# Sheet.net
KiCad netlist of a schematic drawn in Altium Designer
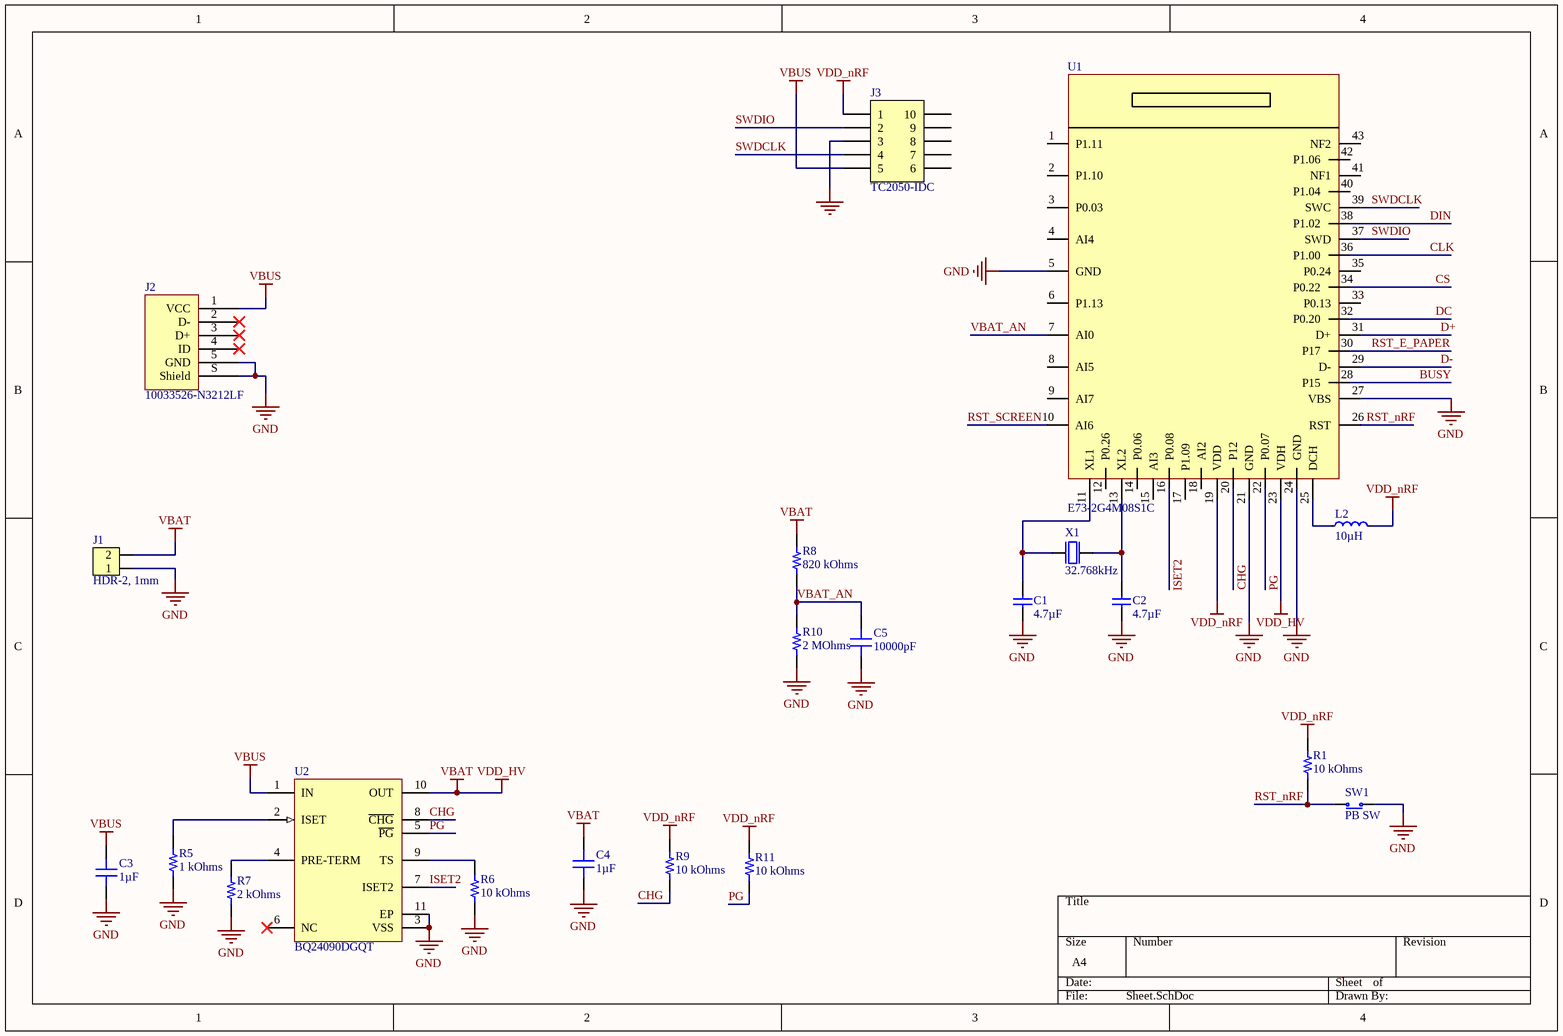
[diagram p0: Sheet.SchDoc]

(export (version "E")
  (design (tool "Eeschema 10.0.6"))
  (components
    (comp (ref "C1")
      (value "4.7µF")
      (footprint "CAPC1608X06L")
      (description "Capacitor, X7R, ±10%")
      (fields
        (field (name "PART NUMBER") "C0603-4µ7-6.3V-X7R")
        (field (name "MANUFACTURER") "Samsung")
        (field (name "PUBLISHER") "Nordic Semiconductor")
      )
      (libsource (lib "pca10056") (part "CAP_0603"))
    )
    (comp (ref "C2")
      (value "4.7µF")
      (footprint "CAPC1608X06L")
      (description "Capacitor, X7R, ±10%")
      (fields
        (field (name "PART NUMBER") "C0603-4µ7-6.3V-X7R")
        (field (name "MANUFACTURER") "Samsung")
        (field (name "PUBLISHER") "Nordic Semiconductor")
      )
      (libsource (lib "pca10056") (part "CAP_0603"))
    )
    (comp (ref "C3")
      (value "1µF")
      (footprint "CAP 0603_1608")
      (description "CAP CER 1UF 6.3V X5R 0603")
      (fields (field (name "PART NUMBER") "JMK107BJ105KK-T") (field (name "MANUFACTURER") "Taiyo Yuden"))
      (libsource (lib "Celestial Altium Library - altium_library") (part "Capacitor"))
    )
    (comp (ref "C4")
      (value "1µF")
      (footprint "CAP 0603_1608")
      (description "CAP CER 1UF 6.3V X5R 0603")
      (fields (field (name "PART NUMBER") "JMK107BJ105KK-T") (field (name "MANUFACTURER") "Taiyo Yuden"))
      (libsource (lib "Celestial Altium Library - altium_library") (part "Capacitor"))
    )
    (comp (ref "C5")
      (value "10000pF")
      (footprint "CAP 0603_1608")
      (description "CAP CER 0603 10NF 16V X7R 10%")
      (fields (field (name "PART NUMBER") "C0603C103K4RECAUTO") (field (name "MANUFACTURER") "KEMET"))
      (libsource (lib "Celestial Altium Library - altium_library") (part "Capacitor"))
    )
    (comp (ref "J1")
      (value "HDR-2, 1mm")
      (footprint "SM02B-SRSS-TB")
      (description "1.0mm pitch connector side entry SMD")
      (fields
        (field (name "PART NUMBER") "SM02B-SRSS-TB")
        (field (name "MANUFACTURER") "JST")
        (field (name "PUBLISHER") "Nordic Semiconductor")
      )
      (libsource (lib "pca10056") (part "SM02B-SRSS-TB"))
    )
    (comp (ref "J2")
      (value "10033526-N3212LF")
      (footprint "FCI USB 10033526-N3212LF")
      (description "CONN RCPT MINI USB B 5POS SMD RA")
      (fields (field (name "MANUFACTURER") "Amphenol ICC (FCI)"))
      (libsource (lib "Celestial Altium Library - altium_library") (part "USB 2.0 Type B Micro"))
    )
    (comp (ref "J3")
      (value "TC2050-IDC")
      (footprint "TC2050-IDC-NLFP")
      (description "CBL PLUG-OF-NAILS 10-PIN")
      (fields
        (field (name "PART NUMBER") "TC2050-IDC-NLFP")
        (field (name "MANUFACTURER") "Tag-Connect LLC")
        (field (name "PUBLISHER") "Nordic Semiconductor")
      )
      (libsource (lib "pca10059") (part "TC2050-IDC"))
    )
    (comp (ref "L2")
      (value "10µH")
      (footprint "INDC1608X06L")
      (description "Inductor, 80mA, ±10%")
      (fields
        (field (name "PART NUMBER") "L0603-10µ")
        (field (name "MANUFACTURER") "Taiyo Yuden")
        (field (name "PUBLISHER") "Nordic Semiconductor")
      )
      (libsource (lib "pca10059") (part "IND_0603"))
    )
    (comp (ref "R1")
      (value "10 kOhms")
      (footprint "RES 0603_1608")
      (description "RES 10K OHM 0.1% 1/16W 0603")
      (fields
        (field (name "PART NUMBER") "RNCS0603BKE10K0")
        (field (name "MANUFACTURER") "Stackpole Electronics Inc")
      )
      (libsource (lib "Celestial Altium Library - altium_library") (part "Resistor"))
    )
    (comp (ref "R5")
      (value "1 kOhms")
      (footprint "RES 0603_1608")
      (description "RES SMD 1K OHM 0.1% 1/16W 0603")
      (fields
        (field (name "PART NUMBER") "CPF0603B1K0E")
        (field (name "MANUFACTURER") "TE Connectivity Passive Product")
      )
      (libsource (lib "Celestial Altium Library - altium_library") (part "Resistor"))
    )
    (comp (ref "R6")
      (value "10 kOhms")
      (footprint "RES 0603_1608")
      (description "RES 10K OHM 0.1% 1/16W 0603")
      (fields
        (field (name "PART NUMBER") "RNCS0603BKE10K0")
        (field (name "MANUFACTURER") "Stackpole Electronics Inc")
      )
      (libsource (lib "Celestial Altium Library - altium_library") (part "Resistor"))
    )
    (comp (ref "R7")
      (value "2 kOhms")
      (footprint "RES 0603_1608")
      (description "RES SMD 2K OHM 0.1% 1/10W 0603")
      (fields (field (name "PART NUMBER") "RT0603BRD072KL") (field (name "MANUFACTURER") "Yageo"))
      (libsource (lib "Celestial Altium Library - altium_library") (part "Resistor"))
    )
    (comp (ref "R8")
      (value "820 kOhms")
      (footprint "RES 0603_1608")
      (description "CRGP 0603 820K 1%")
      (fields
        (field (name "PART NUMBER") "CRGP0603F820K")
        (field (name "MANUFACTURER") "TE Connectivity Passive Product")
      )
      (libsource (lib "Celestial Altium Library - altium_library") (part "Resistor"))
    )
    (comp (ref "R9")
      (value "10 kOhms")
      (footprint "RES 0603_1608")
      (description "RES 10K OHM 0.1% 1/16W 0603")
      (fields
        (field (name "PART NUMBER") "RNCS0603BKE10K0")
        (field (name "MANUFACTURER") "Stackpole Electronics Inc")
      )
      (libsource (lib "Celestial Altium Library - altium_library") (part "Resistor"))
    )
    (comp (ref "R10")
      (value "2 MOhms")
      (footprint "RES 0603_1608")
      (description "RES 2M OHM 1% 1/10W 0603")
      (fields
        (field (name "PART NUMBER") "RMCF0603FT2M00")
        (field (name "MANUFACTURER") "Stackpole Electronics Inc")
      )
      (libsource (lib "Celestial Altium Library - altium_library") (part "Resistor"))
    )
    (comp (ref "R11")
      (value "10 kOhms")
      (footprint "RES 0603_1608")
      (description "RES 10K OHM 0.1% 1/16W 0603")
      (fields
        (field (name "PART NUMBER") "RNCS0603BKE10K0")
        (field (name "MANUFACTURER") "Stackpole Electronics Inc")
      )
      (libsource (lib "Celestial Altium Library - altium_library") (part "Resistor"))
    )
    (comp (ref "SW1")
      (value "PB SW")
      (footprint "Switch-PB-6.2x6.3mm-SMD")
      (description "Tactile Switch, SPNO, SMD, 160gf, 6.2x6.3x2.5mm")
      (fields
        (field (name "PART NUMBER") "Switch-PB-6.2x6.3mm-SMD")
        (field (name "MANUFACTURER") "Dailywell")
        (field (name "PUBLISHER") "Nordic Semiconductor")
      )
      (libsource (lib "pca10056") (part "Switch-PB-6.2x6.3mm-SMD"))
    )
    (comp (ref "U1")
      (value "E73-2G4M08S1C")
      (footprint "E73-2G4M08S1C")
      (libsource (lib "E73-2G4M08S1C") (part "E73-2G4M08S1C"))
    )
    (comp (ref "U2")
      (value "BQ24090DGQT")
      (footprint "DGQ0010D_M")
      (fields (field (name "MANUFACTURER") "Texas Instruments"))
      (libsource (lib "Altium Content Vault") (part "TI-BQ24090DGQ10-1675X1445TP"))
    )
    (comp (ref "X1")
      (value "32.768kHz")
      (footprint "XTAL_3215")
      (description "XTAL SMD 2012, 32.768kHz, 9pF, ±20ppm")
      (fields
        (field (name "PART NUMBER") "XTAL_SMD3215_32.768kHz_9pF_NDK")
        (field (name "MANUFACTURER") "NDK")
        (field (name "PUBLISHER") "Nordic Semiconductor")
      )
      (libsource (lib "pca10056") (part "XTAL_SMD3215"))
    )
  )
  (nets
    (net (code "1") (name "/BUSY") (class "Default")
      (node (ref "U1") (pin "28") (pinfunction "P15_28") (pintype "passive"))
    )
    (net (code "2") (name "/CHG") (class "Default")
      (node (ref "R9") (pin "2") (pinfunction "2_2") (pintype "passive"))
      (node (ref "U1") (pin "20") (pinfunction "P12_20") (pintype "passive"))
      (node (ref "U2") (pin "8") (pinfunction "~{CHG}_8") (pintype "tri_state"))
    )
    (net (code "3") (name "/CLK") (class "Default")
      (node (ref "U1") (pin "36") (pinfunction "P1.00_36") (pintype "passive"))
    )
    (net (code "4") (name "/CS") (class "Default")
      (node (ref "U1") (pin "34") (pinfunction "P0.22_34") (pintype "passive"))
    )
    (net (code "5") (name "/D+") (class "Default")
      (node (ref "U1") (pin "31") (pinfunction "D+_31") (pintype "passive"))
    )
    (net (code "6") (name "/D-") (class "Default")
      (node (ref "U1") (pin "29") (pinfunction "D-_29") (pintype "passive"))
    )
    (net (code "7") (name "/DC") (class "Default")
      (node (ref "U1") (pin "32") (pinfunction "P0.20_32") (pintype "passive"))
    )
    (net (code "8") (name "/DIN") (class "Default")
      (node (ref "U1") (pin "38") (pinfunction "P1.02_38") (pintype "passive"))
    )
    (net (code "9") (name "/ISET2") (class "Default")
      (node (ref "U1") (pin "16") (pinfunction "P0.08_16") (pintype "passive"))
      (node (ref "U2") (pin "7") (pinfunction "ISET2_7") (pintype "passive"))
    )
    (net (code "10") (name "/PG") (class "Default")
      (node (ref "R11") (pin "2") (pinfunction "2_2") (pintype "passive"))
      (node (ref "U1") (pin "22") (pinfunction "P0.07_22") (pintype "passive"))
      (node (ref "U2") (pin "5") (pinfunction "~{PG}_5") (pintype "tri_state"))
    )
    (net (code "11") (name "/RST_E_PAPER") (class "Default")
      (node (ref "U1") (pin "30") (pinfunction "P17_30") (pintype "passive"))
    )
    (net (code "12") (name "/RST_SCREEN") (class "Default")
      (node (ref "U1") (pin "10") (pinfunction "AI6_10") (pintype "passive"))
    )
    (net (code "13") (name "/RST_nRF") (class "Default")
      (node (ref "R1") (pin "2") (pinfunction "2_2") (pintype "passive"))
      (node (ref "SW1") (pin "1") (pinfunction "N.O_1") (pintype "passive"))
      (node (ref "U1") (pin "26") (pinfunction "RST_26") (pintype "passive"))
    )
    (net (code "14") (name "/SWDCLK") (class "Default")
      (node (ref "J3") (pin "4") (pinfunction "4_4") (pintype "passive"))
      (node (ref "U1") (pin "39") (pinfunction "SWC_39") (pintype "passive"))
    )
    (net (code "15") (name "/SWDIO") (class "Default")
      (node (ref "J3") (pin "2") (pinfunction "2_2") (pintype "passive"))
      (node (ref "U1") (pin "37") (pinfunction "SWD_37") (pintype "passive"))
    )
    (net (code "16") (name "/VBAT_AN") (class "Default")
      (node (ref "C5") (pin "2") (pinfunction "2_2") (pintype "passive"))
      (node (ref "R10") (pin "2") (pinfunction "2_2") (pintype "passive"))
      (node (ref "R8") (pin "1") (pinfunction "1_1") (pintype "passive"))
      (node (ref "U1") (pin "7") (pinfunction "AI0_7") (pintype "passive"))
    )
    (net (code "17") (name "GND") (class "Default")
      (node (ref "C1") (pin "1") (pinfunction "1_1") (pintype "passive"))
      (node (ref "C2") (pin "1") (pinfunction "1_1") (pintype "passive"))
      (node (ref "C3") (pin "1") (pinfunction "1_1") (pintype "passive"))
      (node (ref "C4") (pin "1") (pinfunction "1_1") (pintype "passive"))
      (node (ref "C5") (pin "1") (pinfunction "1_1") (pintype "passive"))
      (node (ref "J1") (pin "1") (pinfunction "1_1") (pintype "passive"))
      (node (ref "J2") (pin "5") (pinfunction "GND_5") (pintype "passive"))
      (node (ref "J2") (pin "S") (pinfunction "Shield_S") (pintype "passive"))
      (node (ref "J3") (pin "3") (pinfunction "3_3") (pintype "passive"))
      (node (ref "R10") (pin "1") (pinfunction "1_1") (pintype "passive"))
      (node (ref "R5") (pin "1") (pinfunction "1_1") (pintype "passive"))
      (node (ref "R6") (pin "1") (pinfunction "1_1") (pintype "passive"))
      (node (ref "R7") (pin "1") (pinfunction "1_1") (pintype "passive"))
      (node (ref "SW1") (pin "2") (pinfunction "COM_2") (pintype "passive"))
      (node (ref "U1") (pin "21") (pinfunction "GND_21") (pintype "passive"))
      (node (ref "U1") (pin "24") (pinfunction "GND_24") (pintype "passive"))
      (node (ref "U1") (pin "27") (pinfunction "VBS_27") (pintype "passive"))
      (node (ref "U1") (pin "5") (pinfunction "GND_5") (pintype "passive"))
      (node (ref "U2") (pin "11") (pinfunction "EP_11") (pintype "power_in"))
      (node (ref "U2") (pin "3") (pinfunction "VSS_3") (pintype "power_in"))
    )
    (net (code "18") (name "Net-(U1-DCH)") (class "Default")
      (node (ref "L2") (pin "1") (pinfunction "1_1") (pintype "passive"))
      (node (ref "U1") (pin "25") (pinfunction "DCH_25") (pintype "passive"))
    )
    (net (code "19") (name "Net-(U1-XL1)") (class "Default")
      (node (ref "C1") (pin "2") (pinfunction "2_2") (pintype "passive"))
      (node (ref "U1") (pin "11") (pinfunction "XL1_11") (pintype "passive"))
      (node (ref "X1") (pin "1") (pinfunction "inp_1") (pintype "passive"))
    )
    (net (code "20") (name "Net-(U1-XL2)") (class "Default")
      (node (ref "C2") (pin "2") (pinfunction "2_2") (pintype "passive"))
      (node (ref "U1") (pin "13") (pinfunction "XL2_13") (pintype "passive"))
      (node (ref "X1") (pin "2") (pinfunction "out_2") (pintype "passive"))
    )
    (net (code "21") (name "Net-(U2-ISET)") (class "Default")
      (node (ref "R5") (pin "2") (pinfunction "2_2") (pintype "passive"))
      (node (ref "U2") (pin "2") (pinfunction "ISET_2") (pintype "input"))
    )
    (net (code "22") (name "Net-(U2-PRE-TERM)") (class "Default")
      (node (ref "R7") (pin "2") (pinfunction "2_2") (pintype "passive"))
      (node (ref "U2") (pin "4") (pinfunction "PRE-TERM_4") (pintype "passive"))
    )
    (net (code "23") (name "Net-(U2-TS)") (class "Default")
      (node (ref "R6") (pin "2") (pinfunction "2_2") (pintype "passive"))
      (node (ref "U2") (pin "9") (pinfunction "TS_9") (pintype "passive"))
    )
    (net (code "24") (name "VBAT") (class "Default")
      (node (ref "C4") (pin "2") (pinfunction "2_2") (pintype "passive"))
      (node (ref "J1") (pin "2") (pinfunction "2_2") (pintype "passive"))
      (node (ref "R8") (pin "2") (pinfunction "2_2") (pintype "passive"))
      (node (ref "U1") (pin "23") (pinfunction "VDH_23") (pintype "passive"))
      (node (ref "U2") (pin "10") (pinfunction "OUT_10") (pintype "power_in"))
    )
    (net (code "25") (name "VBUS") (class "Default")
      (node (ref "C3") (pin "2") (pinfunction "2_2") (pintype "passive"))
      (node (ref "J2") (pin "1") (pinfunction "VCC_1") (pintype "passive"))
      (node (ref "J3") (pin "5") (pinfunction "5_5") (pintype "passive"))
      (node (ref "U2") (pin "1") (pinfunction "IN_1") (pintype "power_in"))
    )
    (net (code "26") (name "VDD_nRF") (class "Default")
      (node (ref "J3") (pin "1") (pinfunction "1_1") (pintype "passive"))
      (node (ref "L2") (pin "2") (pinfunction "2_2") (pintype "passive"))
      (node (ref "R1") (pin "1") (pinfunction "1_1") (pintype "passive"))
      (node (ref "R11") (pin "1") (pinfunction "1_1") (pintype "passive"))
      (node (ref "R9") (pin "1") (pinfunction "1_1") (pintype "passive"))
      (node (ref "U1") (pin "19") (pinfunction "VDD_19") (pintype "passive"))
    )
    (net (code "27") (name "unconnected-(J2-D+-Pad3)") (class "Default")
      (node (ref "J2") (pin "3") (pinfunction "D+_3") (pintype "passive+no_connect"))
    )
    (net (code "28") (name "unconnected-(J2-D--Pad2)") (class "Default")
      (node (ref "J2") (pin "2") (pinfunction "D-_2") (pintype "passive+no_connect"))
    )
    (net (code "29") (name "unconnected-(J2-ID-Pad4)") (class "Default")
      (node (ref "J2") (pin "4") (pinfunction "ID_4") (pintype "passive+no_connect"))
    )
    (net (code "30") (name "unconnected-(J3-Pad6)") (class "Default")
      (node (ref "J3") (pin "6") (pinfunction "6_6") (pintype "passive"))
    )
    (net (code "31") (name "unconnected-(J3-Pad7)") (class "Default")
      (node (ref "J3") (pin "7") (pinfunction "7_7") (pintype "passive"))
    )
    (net (code "32") (name "unconnected-(J3-Pad8)") (class "Default")
      (node (ref "J3") (pin "8") (pinfunction "8_8") (pintype "passive"))
    )
    (net (code "33") (name "unconnected-(J3-Pad9)") (class "Default")
      (node (ref "J3") (pin "9") (pinfunction "9_9") (pintype "passive"))
    )
    (net (code "34") (name "unconnected-(J3-Pad10)") (class "Default")
      (node (ref "J3") (pin "10") (pinfunction "10_10") (pintype "passive"))
    )
    (net (code "35") (name "unconnected-(U1-AI2-Pad18)") (class "Default")
      (node (ref "U1") (pin "18") (pinfunction "AI2_18") (pintype "passive"))
    )
    (net (code "36") (name "unconnected-(U1-AI3-Pad15)") (class "Default")
      (node (ref "U1") (pin "15") (pinfunction "AI3_15") (pintype "passive"))
    )
    (net (code "37") (name "unconnected-(U1-AI4-Pad4)") (class "Default")
      (node (ref "U1") (pin "4") (pinfunction "AI4_4") (pintype "passive"))
    )
    (net (code "38") (name "unconnected-(U1-AI5-Pad8)") (class "Default")
      (node (ref "U1") (pin "8") (pinfunction "AI5_8") (pintype "passive"))
    )
    (net (code "39") (name "unconnected-(U1-AI7-Pad9)") (class "Default")
      (node (ref "U1") (pin "9") (pinfunction "AI7_9") (pintype "passive"))
    )
    (net (code "40") (name "unconnected-(U1-NF1-Pad41)") (class "Default")
      (node (ref "U1") (pin "41") (pinfunction "NF1_41") (pintype "passive"))
    )
    (net (code "41") (name "unconnected-(U1-NF2-Pad43)") (class "Default")
      (node (ref "U1") (pin "43") (pinfunction "NF2_43") (pintype "passive"))
    )
    (net (code "42") (name "unconnected-(U1-P0.03-Pad3)") (class "Default")
      (node (ref "U1") (pin "3") (pinfunction "P0.03_3") (pintype "passive"))
    )
    (net (code "43") (name "unconnected-(U1-P0.06-Pad14)") (class "Default")
      (node (ref "U1") (pin "14") (pinfunction "P0.06_14") (pintype "passive"))
    )
    (net (code "44") (name "unconnected-(U1-P0.13-Pad33)") (class "Default")
      (node (ref "U1") (pin "33") (pinfunction "P0.13_33") (pintype "passive"))
    )
    (net (code "45") (name "unconnected-(U1-P0.24-Pad35)") (class "Default")
      (node (ref "U1") (pin "35") (pinfunction "P0.24_35") (pintype "passive"))
    )
    (net (code "46") (name "unconnected-(U1-P0.26-Pad12)") (class "Default")
      (node (ref "U1") (pin "12") (pinfunction "P0.26_12") (pintype "passive"))
    )
    (net (code "47") (name "unconnected-(U1-P1.04-Pad40)") (class "Default")
      (node (ref "U1") (pin "40") (pinfunction "P1.04_40") (pintype "passive"))
    )
    (net (code "48") (name "unconnected-(U1-P1.06-Pad42)") (class "Default")
      (node (ref "U1") (pin "42") (pinfunction "P1.06_42") (pintype "passive"))
    )
    (net (code "49") (name "unconnected-(U1-P1.09-Pad17)") (class "Default")
      (node (ref "U1") (pin "17") (pinfunction "P1.09_17") (pintype "passive"))
    )
    (net (code "50") (name "unconnected-(U1-P1.10-Pad2)") (class "Default")
      (node (ref "U1") (pin "2") (pinfunction "P1.10_2") (pintype "passive"))
    )
    (net (code "51") (name "unconnected-(U1-P1.11-Pad1)") (class "Default")
      (node (ref "U1") (pin "1") (pinfunction "P1.11_1") (pintype "passive"))
    )
    (net (code "52") (name "unconnected-(U1-P1.13-Pad6)") (class "Default")
      (node (ref "U1") (pin "6") (pinfunction "P1.13_6") (pintype "passive"))
    )
    (net (code "53") (name "unconnected-(U2-NC-Pad6)") (class "Default")
      (node (ref "U2") (pin "6") (pinfunction "NC_6") (pintype "passive+no_connect"))
    )
  )
)
